# Sheet1.net
KiCad netlist of a schematic drawn in Altium Designer
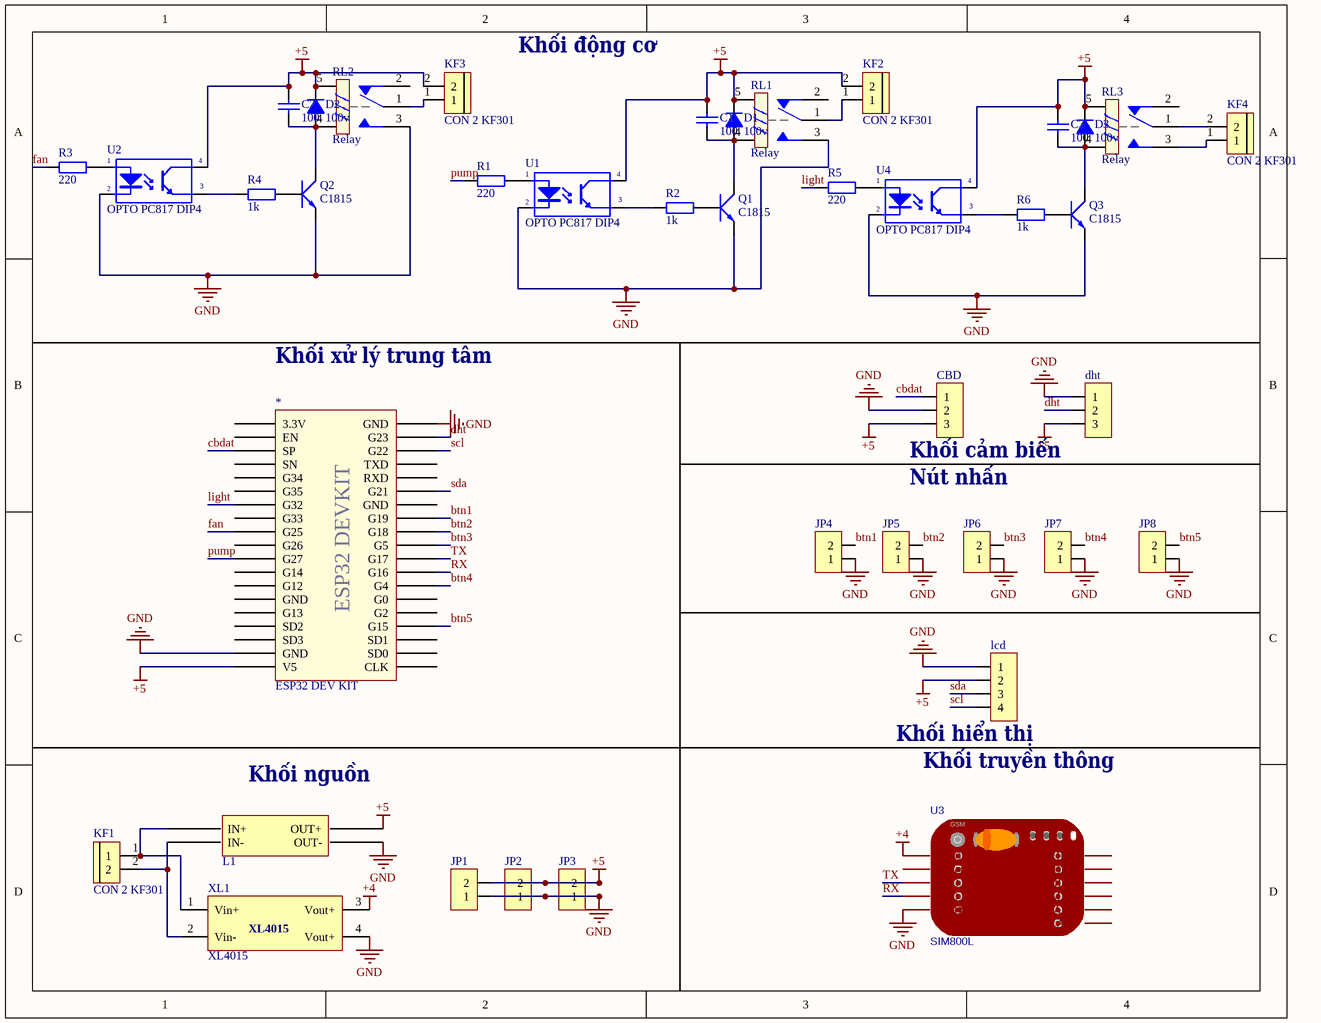
[diagram p0: Sheet1.SchDoc]

(export (version "E")
  (design (tool "Eeschema 10.0.6"))
  (components
    (comp (ref "*")
      (value "ESP32 DEV KIT")
      (footprint "ESP32 DEVKIT")
      (libsource (lib "Altium_Lib_by_KhueNguyenCreator") (part "ESP32 DEV KIT"))
    )
    (comp (ref "C1")
      (value "100")
      (footprint "tu gom")
      (description "Cắm")
      (libsource (lib "Altium_Lib_by_KhueNguyenCreator") (part "Tu gom 100 50V"))
    )
    (comp (ref "C2")
      (value "100")
      (footprint "tu gom")
      (description "Cắm")
      (libsource (lib "Altium_Lib_by_KhueNguyenCreator") (part "Tu gom 100 50V"))
    )
    (comp (ref "C3")
      (value "100")
      (footprint "tu gom")
      (description "Cắm")
      (libsource (lib "Altium_Lib_by_KhueNguyenCreator") (part "Tu gom 100 50V"))
    )
    (comp (ref "CBD")
      (value "JP 1x3 2.54")
      (footprint "JP 1x3 DT")
      (description "Cắm")
      (libsource (lib "Altium_Lib_by_KhueNguyenCreator") (part "JP 1x3 2.54 Duc Thang"))
    )
    (comp (ref "D1")
      (value "100v")
      (footprint "DIODE 1A")
      (description "Cắm")
      (libsource (lib "Altium_Lib_by_KhueNguyenCreator") (part "Diode 1N4007"))
    )
    (comp (ref "D2")
      (value "100v")
      (footprint "DIODE 1A")
      (description "Cắm")
      (libsource (lib "Altium_Lib_by_KhueNguyenCreator") (part "Diode 1N4007"))
    )
    (comp (ref "D3")
      (value "100v")
      (footprint "DIODE 1A")
      (description "Cắm")
      (libsource (lib "Altium_Lib_by_KhueNguyenCreator") (part "Diode 1N4007"))
    )
    (comp (ref "dht")
      (value "JP 1x3 2.54")
      (footprint "JP 1x3 DT")
      (description "Cắm")
      (libsource (lib "Altium_Lib_by_KhueNguyenCreator") (part "JP 1x3 2.54 Duc Thang"))
    )
    (comp (ref "JP1")
      (value "JP 1x2 2.54")
      (footprint "JP 1x2 DT")
      (description "Cắm")
      (libsource (lib "Altium_Lib_by_KhueNguyenCreator") (part "JP 1x2 2.54 Duc Thang"))
    )
    (comp (ref "JP2")
      (value "JP 1x2 2.54")
      (footprint "JP 1x2 DT")
      (description "Cắm")
      (libsource (lib "Altium_Lib_by_KhueNguyenCreator") (part "JP 1x2 2.54 Duc Thang"))
    )
    (comp (ref "JP3")
      (value "JP 1x2 2.54")
      (footprint "JP 1x2 DT")
      (description "Cắm")
      (libsource (lib "Altium_Lib_by_KhueNguyenCreator") (part "JP 1x2 2.54 Duc Thang"))
    )
    (comp (ref "JP4")
      (value "JP 1x2 2.54")
      (footprint "JP 1x2 DT")
      (description "Cắm")
      (libsource (lib "Altium_Lib_by_KhueNguyenCreator") (part "JP 1x2 2.54 Duc Thang"))
    )
    (comp (ref "JP5")
      (value "JP 1x2 2.54")
      (footprint "JP 1x2 DT")
      (description "Cắm")
      (libsource (lib "Altium_Lib_by_KhueNguyenCreator") (part "JP 1x2 2.54 Duc Thang"))
    )
    (comp (ref "JP6")
      (value "JP 1x2 2.54")
      (footprint "JP 1x2 DT")
      (description "Cắm")
      (libsource (lib "Altium_Lib_by_KhueNguyenCreator") (part "JP 1x2 2.54 Duc Thang"))
    )
    (comp (ref "JP7")
      (value "JP 1x2 2.54")
      (footprint "JP 1x2 DT")
      (description "Cắm")
      (libsource (lib "Altium_Lib_by_KhueNguyenCreator") (part "JP 1x2 2.54 Duc Thang"))
    )
    (comp (ref "JP8")
      (value "JP 1x2 2.54")
      (footprint "JP 1x2 DT")
      (description "Cắm")
      (libsource (lib "Altium_Lib_by_KhueNguyenCreator") (part "JP 1x2 2.54 Duc Thang"))
    )
    (comp (ref "KF1")
      (value "CON 2 KF301")
      (footprint "Con 2 KF301 5.08")
      (description "Cắm")
      (libsource (lib "") (part "CON 2 KF301_1"))
    )
    (comp (ref "KF2")
      (value "CON 2 KF301")
      (footprint "Con 2 KF301 5.08")
      (description "Cắm")
      (libsource (lib "Altium_Lib_by_KhueNguyenCreator") (part "CON 2 KF301"))
    )
    (comp (ref "KF3")
      (value "CON 2 KF301")
      (footprint "Con 2 KF301 5.08")
      (description "Cắm")
      (libsource (lib "Altium_Lib_by_KhueNguyenCreator") (part "CON 2 KF301"))
    )
    (comp (ref "KF4")
      (value "CON 2 KF301")
      (footprint "Con 2 KF301 5.08")
      (description "Cắm")
      (libsource (lib "Altium_Lib_by_KhueNguyenCreator") (part "CON 2 KF301"))
    )
    (comp (ref "L1")
      (value "BUCK_LM2596")
      (footprint "BUCK_LM2596")
      (libsource (lib "BUCK_LM2596_Sch") (part "BUCK_LM2596"))
    )
    (comp (ref "lcd")
      (value "JP 1x4 2.54")
      (footprint "JP 1x4 DT")
      (description "Cắm")
      (libsource (lib "Altium_Lib_by_KhueNguyenCreator") (part "JP 1x4 2.54 Duc Thang"))
    )
    (comp (ref "Q1")
      (value "C1815")
      (footprint "TO92")
      (description "NPN transistor")
      (libsource (lib "Altium_Lib_by_KhueNguyenCreator") (part "C1815"))
    )
    (comp (ref "Q2")
      (value "C1815")
      (footprint "TO92")
      (description "NPN transistor")
      (libsource (lib "Altium_Lib_by_KhueNguyenCreator") (part "C1815"))
    )
    (comp (ref "Q3")
      (value "C1815")
      (footprint "TO92")
      (description "NPN transistor")
      (libsource (lib "Altium_Lib_by_KhueNguyenCreator") (part "C1815"))
    )
    (comp (ref "R1")
      (value "220")
      (footprint "tro vach 1/4w")
      (description "Cắm")
      (libsource (lib "Altium_Lib_by_KhueNguyenCreator") (part "Tro Vach 1/4W 5% 1.2R"))
    )
    (comp (ref "R2")
      (value "1k")
      (footprint "tro vach 1/4w")
      (description "Cắm")
      (libsource (lib "Altium_Lib_by_KhueNguyenCreator") (part "Tro Vach 1/4W 5% 1.2R"))
    )
    (comp (ref "R3")
      (value "220")
      (footprint "tro vach 1/4w")
      (description "Cắm")
      (libsource (lib "Altium_Lib_by_KhueNguyenCreator") (part "Tro Vach 1/4W 5% 1.2R"))
    )
    (comp (ref "R4")
      (value "1k")
      (footprint "tro vach 1/4w")
      (description "Cắm")
      (libsource (lib "Altium_Lib_by_KhueNguyenCreator") (part "Tro Vach 1/4W 5% 1.2R"))
    )
    (comp (ref "R5")
      (value "220")
      (footprint "tro vach 1/4w")
      (description "Cắm")
      (libsource (lib "Altium_Lib_by_KhueNguyenCreator") (part "Tro Vach 1/4W 5% 1.2R"))
    )
    (comp (ref "R6")
      (value "1k")
      (footprint "tro vach 1/4w")
      (description "Cắm")
      (libsource (lib "Altium_Lib_by_KhueNguyenCreator") (part "Tro Vach 1/4W 5% 1.2R"))
    )
    (comp (ref "RL1")
      (value "Relay")
      (footprint "Relay 5 Chan SRD")
      (description "Relay 5 Chan")
      (libsource (lib "Altium_Lib_by_KhueNguyenCreator") (part "Relay 5 Chan SRD"))
    )
    (comp (ref "RL2")
      (value "Relay")
      (footprint "Relay 5 Chan SRD")
      (description "Relay 5 Chan")
      (libsource (lib "Altium_Lib_by_KhueNguyenCreator") (part "Relay 5 Chan SRD"))
    )
    (comp (ref "RL3")
      (value "Relay")
      (footprint "Relay 5 Chan SRD")
      (description "Relay 5 Chan")
      (libsource (lib "Altium_Lib_by_KhueNguyenCreator") (part "Relay 5 Chan SRD"))
    )
    (comp (ref "U1")
      (value "OPTO PC817 DIP4")
      (footprint "DIP4")
      (description "Single Opto")
      (libsource (lib "Altium_Lib_by_KhueNguyenCreator") (part "OPTO PC817 DIP4"))
    )
    (comp (ref "U2")
      (value "OPTO PC817 DIP4")
      (footprint "DIP4")
      (description "Single Opto")
      (libsource (lib "Altium_Lib_by_KhueNguyenCreator") (part "OPTO PC817 DIP4"))
    )
    (comp (ref "U3")
      (value "SIM800L")
      (footprint "SIM800L MODULE")
      (fields (field (name "BOM_SUPPLIER PART") "B01DLIJM2E") (field (name "CONTRIBUTOR") "trigui"))
      (libsource (lib "PCB_Project1") (part "SIM800L"))
    )
    (comp (ref "U4")
      (value "OPTO PC817 DIP4")
      (footprint "DIP4")
      (description "Single Opto")
      (libsource (lib "Altium_Lib_by_KhueNguyenCreator") (part "OPTO PC817 DIP4"))
    )
    (comp (ref "XL1") (value "XL4015") (footprint "XL4015") (libsource (lib "XL4015") (part "XL4015")))
  )
  (nets
    (net (code "1") (name "+4") (class "Default")
      (node (ref "U3") (pin "1") (pinfunction "VCC_1") (pintype "passive"))
      (node (ref "XL1") (pin "3") (pinfunction "Vout+_3") (pintype "passive"))
    )
    (net (code "2") (name "+5") (class "Default")
      (node (ref "*") (pin "19") (pinfunction "V5_19") (pintype "passive"))
      (node (ref "C1") (pin "1") (pinfunction "1_1") (pintype "passive"))
      (node (ref "C2") (pin "1") (pinfunction "1_1") (pintype "passive"))
      (node (ref "C3") (pin "1") (pinfunction "1_1") (pintype "passive"))
      (node (ref "CBD") (pin "3") (pinfunction "3_3") (pintype "passive"))
      (node (ref "D1") (pin "2") (pinfunction "K_2") (pintype "passive"))
      (node (ref "D2") (pin "2") (pinfunction "K_2") (pintype "passive"))
      (node (ref "D3") (pin "2") (pinfunction "K_2") (pintype "passive"))
      (node (ref "JP1") (pin "2") (pinfunction "2_2") (pintype "passive"))
      (node (ref "JP2") (pin "2") (pinfunction "2_2") (pintype "passive"))
      (node (ref "JP3") (pin "2") (pinfunction "2_2") (pintype "passive"))
      (node (ref "KF2") (pin "2") (pinfunction "2_2") (pintype "passive"))
      (node (ref "KF3") (pin "2") (pinfunction "2_2") (pintype "passive"))
      (node (ref "L1") (pin "4") (pinfunction "OUT+_4") (pintype "passive"))
      (node (ref "RL1") (pin "5") (pinfunction "5_5") (pintype "passive"))
      (node (ref "RL2") (pin "5") (pinfunction "5_5") (pintype "passive"))
      (node (ref "RL3") (pin "5") (pinfunction "5_5") (pintype "passive"))
      (node (ref "U1") (pin "4") (pinfunction "C_4") (pintype "passive"))
      (node (ref "U2") (pin "4") (pinfunction "C_4") (pintype "passive"))
      (node (ref "U4") (pin "4") (pinfunction "C_4") (pintype "passive"))
      (node (ref "dht") (pin "3") (pinfunction "3_3") (pintype "passive"))
      (node (ref "lcd") (pin "2") (pinfunction "2_2") (pintype "passive"))
    )
    (net (code "3") (name "/RX") (class "Default")
      (node (ref "*") (pin "27") (pinfunction "G16_27") (pintype "passive"))
      (node (ref "U3") (pin "4") (pinfunction "TxD_4") (pintype "passive"))
    )
    (net (code "4") (name "/TX") (class "Default")
      (node (ref "*") (pin "28") (pinfunction "G17_28") (pintype "passive"))
      (node (ref "U3") (pin "3") (pinfunction "RxD_3") (pintype "passive"))
    )
    (net (code "5") (name "/btn1") (class "Default")
      (node (ref "*") (pin "31") (pinfunction "G19_31") (pintype "passive"))
      (node (ref "JP4") (pin "2") (pinfunction "2_2") (pintype "passive"))
    )
    (net (code "6") (name "/btn2") (class "Default")
      (node (ref "*") (pin "30") (pinfunction "G18_30") (pintype "passive"))
      (node (ref "JP5") (pin "2") (pinfunction "2_2") (pintype "passive"))
    )
    (net (code "7") (name "/btn3") (class "Default")
      (node (ref "*") (pin "29") (pinfunction "G5_29") (pintype "passive"))
      (node (ref "JP6") (pin "2") (pinfunction "2_2") (pintype "passive"))
    )
    (net (code "8") (name "/btn4") (class "Default")
      (node (ref "*") (pin "26") (pinfunction "G4_26") (pintype "passive"))
      (node (ref "JP7") (pin "2") (pinfunction "2_2") (pintype "passive"))
    )
    (net (code "9") (name "/btn5") (class "Default")
      (node (ref "*") (pin "23") (pinfunction "G15_23") (pintype "passive"))
      (node (ref "JP8") (pin "2") (pinfunction "2_2") (pintype "passive"))
    )
    (net (code "10") (name "/cbdat") (class "Default")
      (node (ref "*") (pin "3") (pinfunction "SP_3") (pintype "passive"))
      (node (ref "CBD") (pin "1") (pinfunction "1_1") (pintype "passive"))
    )
    (net (code "11") (name "/dht") (class "Default")
      (node (ref "*") (pin "37") (pinfunction "G23_37") (pintype "passive"))
      (node (ref "dht") (pin "2") (pinfunction "2_2") (pintype "passive"))
    )
    (net (code "12") (name "/fan") (class "Default")
      (node (ref "*") (pin "9") (pinfunction "G25_9") (pintype "passive"))
      (node (ref "R3") (pin "1") (pinfunction "1_1") (pintype "passive"))
    )
    (net (code "13") (name "/light") (class "Default")
      (node (ref "*") (pin "7") (pinfunction "G32_7") (pintype "passive"))
      (node (ref "R5") (pin "1") (pinfunction "1_1") (pintype "passive"))
    )
    (net (code "14") (name "/pump") (class "Default")
      (node (ref "*") (pin "11") (pinfunction "G27_11") (pintype "passive"))
      (node (ref "R1") (pin "1") (pinfunction "1_1") (pintype "passive"))
    )
    (net (code "15") (name "/scl") (class "Default")
      (node (ref "*") (pin "36") (pinfunction "G22_36") (pintype "passive"))
      (node (ref "lcd") (pin "4") (pinfunction "4_4") (pintype "passive"))
    )
    (net (code "16") (name "/sda") (class "Default")
      (node (ref "*") (pin "33") (pinfunction "G21_33") (pintype "passive"))
      (node (ref "lcd") (pin "3") (pinfunction "3_3") (pintype "passive"))
    )
    (net (code "17") (name "GND") (class "Default")
      (node (ref "*") (pin "18") (pinfunction "GND_18") (pintype "passive"))
      (node (ref "*") (pin "38") (pinfunction "GND_38") (pintype "passive"))
      (node (ref "CBD") (pin "2") (pinfunction "2_2") (pintype "passive"))
      (node (ref "JP1") (pin "1") (pinfunction "1_1") (pintype "passive"))
      (node (ref "JP2") (pin "1") (pinfunction "1_1") (pintype "passive"))
      (node (ref "JP3") (pin "1") (pinfunction "1_1") (pintype "passive"))
      (node (ref "JP4") (pin "1") (pinfunction "1_1") (pintype "passive"))
      (node (ref "JP5") (pin "1") (pinfunction "1_1") (pintype "passive"))
      (node (ref "JP6") (pin "1") (pinfunction "1_1") (pintype "passive"))
      (node (ref "JP7") (pin "1") (pinfunction "1_1") (pintype "passive"))
      (node (ref "JP8") (pin "1") (pinfunction "1_1") (pintype "passive"))
      (node (ref "L1") (pin "3") (pinfunction "OUT-_3") (pintype "passive"))
      (node (ref "Q1") (pin "1") (pinfunction "E_1") (pintype "passive"))
      (node (ref "Q2") (pin "1") (pinfunction "E_1") (pintype "passive"))
      (node (ref "Q3") (pin "1") (pinfunction "E_1") (pintype "passive"))
      (node (ref "RL1") (pin "3") (pinfunction "3_3") (pintype "passive"))
      (node (ref "RL2") (pin "3") (pinfunction "3_3") (pintype "passive"))
      (node (ref "U1") (pin "2") (pinfunction "K_2") (pintype "passive"))
      (node (ref "U2") (pin "2") (pinfunction "K_2") (pintype "passive"))
      (node (ref "U3") (pin "5") (pinfunction "GND_5") (pintype "passive"))
      (node (ref "U4") (pin "2") (pinfunction "K_2") (pintype "passive"))
      (node (ref "XL1") (pin "4") (pinfunction "Vout+_4") (pintype "passive"))
      (node (ref "dht") (pin "1") (pinfunction "1_1") (pintype "passive"))
      (node (ref "lcd") (pin "1") (pinfunction "1_1") (pintype "passive"))
    )
    (net (code "18") (name "Net-(D1-A)") (class "Default")
      (node (ref "C1") (pin "2") (pinfunction "2_2") (pintype "passive"))
      (node (ref "D1") (pin "1") (pinfunction "A_1") (pintype "passive"))
      (node (ref "Q1") (pin "2") (pinfunction "C_2") (pintype "passive"))
      (node (ref "RL1") (pin "4") (pinfunction "4_4") (pintype "passive"))
    )
    (net (code "19") (name "Net-(D2-A)") (class "Default")
      (node (ref "C2") (pin "2") (pinfunction "2_2") (pintype "passive"))
      (node (ref "D2") (pin "1") (pinfunction "A_1") (pintype "passive"))
      (node (ref "Q2") (pin "2") (pinfunction "C_2") (pintype "passive"))
      (node (ref "RL2") (pin "4") (pinfunction "4_4") (pintype "passive"))
    )
    (net (code "20") (name "Net-(D3-A)") (class "Default")
      (node (ref "C3") (pin "2") (pinfunction "2_2") (pintype "passive"))
      (node (ref "D3") (pin "1") (pinfunction "A_1") (pintype "passive"))
      (node (ref "Q3") (pin "2") (pinfunction "C_2") (pintype "passive"))
      (node (ref "RL3") (pin "4") (pinfunction "4_4") (pintype "passive"))
    )
    (net (code "21") (name "Net-(KF2-Pad1)") (class "Default")
      (node (ref "KF2") (pin "1") (pinfunction "1_1") (pintype "passive"))
      (node (ref "RL1") (pin "1") (pinfunction "1_1") (pintype "passive"))
    )
    (net (code "22") (name "Net-(KF3-Pad1)") (class "Default")
      (node (ref "KF3") (pin "1") (pinfunction "1_1") (pintype "passive"))
      (node (ref "RL2") (pin "1") (pinfunction "1_1") (pintype "passive"))
    )
    (net (code "23") (name "Net-(KF4-Pad1)") (class "Default")
      (node (ref "KF4") (pin "1") (pinfunction "1_1") (pintype "passive"))
      (node (ref "RL3") (pin "3") (pinfunction "3_3") (pintype "passive"))
    )
    (net (code "24") (name "Net-(KF4-Pad2)") (class "Default")
      (node (ref "KF4") (pin "2") (pinfunction "2_2") (pintype "passive"))
      (node (ref "RL3") (pin "1") (pinfunction "1_1") (pintype "passive"))
    )
    (net (code "25") (name "Net-(L1-IN+)") (class "Default")
      (node (ref "KF1") (pin "1") (pinfunction "1_1") (pintype "passive"))
      (node (ref "L1") (pin "1") (pinfunction "IN+_1") (pintype "passive"))
      (node (ref "XL1") (pin "1") (pinfunction "Vin+_1") (pintype "passive"))
    )
    (net (code "26") (name "Net-(L1-IN-)") (class "Default")
      (node (ref "KF1") (pin "2") (pinfunction "2_2") (pintype "passive"))
      (node (ref "L1") (pin "2") (pinfunction "IN-_2") (pintype "passive"))
      (node (ref "XL1") (pin "2") (pinfunction "Vin-_2") (pintype "passive"))
    )
    (net (code "27") (name "Net-(Q1-B)") (class "Default")
      (node (ref "Q1") (pin "3") (pinfunction "B_3") (pintype "passive"))
      (node (ref "R2") (pin "2") (pinfunction "2_2") (pintype "passive"))
    )
    (net (code "28") (name "Net-(Q2-B)") (class "Default")
      (node (ref "Q2") (pin "3") (pinfunction "B_3") (pintype "passive"))
      (node (ref "R4") (pin "2") (pinfunction "2_2") (pintype "passive"))
    )
    (net (code "29") (name "Net-(Q3-B)") (class "Default")
      (node (ref "Q3") (pin "3") (pinfunction "B_3") (pintype "passive"))
      (node (ref "R6") (pin "2") (pinfunction "2_2") (pintype "passive"))
    )
    (net (code "30") (name "Net-(U1-A)") (class "Default")
      (node (ref "R1") (pin "2") (pinfunction "2_2") (pintype "passive"))
      (node (ref "U1") (pin "1") (pinfunction "A_1") (pintype "passive"))
    )
    (net (code "31") (name "Net-(U1-E)") (class "Default")
      (node (ref "R2") (pin "1") (pinfunction "1_1") (pintype "passive"))
      (node (ref "U1") (pin "3") (pinfunction "E_3") (pintype "passive"))
    )
    (net (code "32") (name "Net-(U2-A)") (class "Default")
      (node (ref "R3") (pin "2") (pinfunction "2_2") (pintype "passive"))
      (node (ref "U2") (pin "1") (pinfunction "A_1") (pintype "passive"))
    )
    (net (code "33") (name "Net-(U2-E)") (class "Default")
      (node (ref "R4") (pin "1") (pinfunction "1_1") (pintype "passive"))
      (node (ref "U2") (pin "3") (pinfunction "E_3") (pintype "passive"))
    )
    (net (code "34") (name "Net-(U4-A)") (class "Default")
      (node (ref "R5") (pin "2") (pinfunction "2_2") (pintype "passive"))
      (node (ref "U4") (pin "1") (pinfunction "A_1") (pintype "passive"))
    )
    (net (code "35") (name "Net-(U4-E)") (class "Default")
      (node (ref "R6") (pin "1") (pinfunction "1_1") (pintype "passive"))
      (node (ref "U4") (pin "3") (pinfunction "E_3") (pintype "passive"))
    )
    (net (code "36") (name "unconnected-(*-3.3V-Pad1)") (class "Default")
      (node (ref "*") (pin "1") (pinfunction "3.3V_1") (pintype "passive"))
    )
    (net (code "37") (name "unconnected-(*-CLK-Pad20)") (class "Default")
      (node (ref "*") (pin "20") (pinfunction "CLK_20") (pintype "passive"))
    )
    (net (code "38") (name "unconnected-(*-EN-Pad2)") (class "Default")
      (node (ref "*") (pin "2") (pinfunction "EN_2") (pintype "passive"))
    )
    (net (code "39") (name "unconnected-(*-G0-Pad25)") (class "Default")
      (node (ref "*") (pin "25") (pinfunction "G0_25") (pintype "passive"))
    )
    (net (code "40") (name "unconnected-(*-G2-Pad24)") (class "Default")
      (node (ref "*") (pin "24") (pinfunction "G2_24") (pintype "passive"))
    )
    (net (code "41") (name "unconnected-(*-G12-Pad13)") (class "Default")
      (node (ref "*") (pin "13") (pinfunction "G12_13") (pintype "passive"))
    )
    (net (code "42") (name "unconnected-(*-G13-Pad15)") (class "Default")
      (node (ref "*") (pin "15") (pinfunction "G13_15") (pintype "passive"))
    )
    (net (code "43") (name "unconnected-(*-G14-Pad12)") (class "Default")
      (node (ref "*") (pin "12") (pinfunction "G14_12") (pintype "passive"))
    )
    (net (code "44") (name "unconnected-(*-G26-Pad10)") (class "Default")
      (node (ref "*") (pin "10") (pinfunction "G26_10") (pintype "passive"))
    )
    (net (code "45") (name "unconnected-(*-G33-Pad8)") (class "Default")
      (node (ref "*") (pin "8") (pinfunction "G33_8") (pintype "passive"))
    )
    (net (code "46") (name "unconnected-(*-G34-Pad5)") (class "Default")
      (node (ref "*") (pin "5") (pinfunction "G34_5") (pintype "passive"))
    )
    (net (code "47") (name "unconnected-(*-G35-Pad6)") (class "Default")
      (node (ref "*") (pin "6") (pinfunction "G35_6") (pintype "passive"))
    )
    (net (code "48") (name "unconnected-(*-GND-Pad14)") (class "Default")
      (node (ref "*") (pin "14") (pinfunction "GND_14") (pintype "passive"))
    )
    (net (code "49") (name "unconnected-(*-GND-Pad32)") (class "Default")
      (node (ref "*") (pin "32") (pinfunction "GND_32") (pintype "passive"))
    )
    (net (code "50") (name "unconnected-(*-RXD-Pad34)") (class "Default")
      (node (ref "*") (pin "34") (pinfunction "RXD_34") (pintype "passive"))
    )
    (net (code "51") (name "unconnected-(*-SD0-Pad21)") (class "Default")
      (node (ref "*") (pin "21") (pinfunction "SD0_21") (pintype "passive"))
    )
    (net (code "52") (name "unconnected-(*-SD1-Pad22)") (class "Default")
      (node (ref "*") (pin "22") (pinfunction "SD1_22") (pintype "passive"))
    )
    (net (code "53") (name "unconnected-(*-SD2-Pad16)") (class "Default")
      (node (ref "*") (pin "16") (pinfunction "SD2_16") (pintype "passive"))
    )
    (net (code "54") (name "unconnected-(*-SD3-Pad17)") (class "Default")
      (node (ref "*") (pin "17") (pinfunction "SD3_17") (pintype "passive"))
    )
    (net (code "55") (name "unconnected-(*-SN-Pad4)") (class "Default")
      (node (ref "*") (pin "4") (pinfunction "SN_4") (pintype "passive"))
    )
    (net (code "56") (name "unconnected-(*-TXD-Pad35)") (class "Default")
      (node (ref "*") (pin "35") (pinfunction "TXD_35") (pintype "passive"))
    )
    (net (code "57") (name "unconnected-(RL1-Pad2)") (class "Default")
      (node (ref "RL1") (pin "2") (pinfunction "2_2") (pintype "passive"))
    )
    (net (code "58") (name "unconnected-(RL2-Pad2)") (class "Default")
      (node (ref "RL2") (pin "2") (pinfunction "2_2") (pintype "passive"))
    )
    (net (code "59") (name "unconnected-(RL3-Pad2)") (class "Default")
      (node (ref "RL3") (pin "2") (pinfunction "2_2") (pintype "passive"))
    )
    (net (code "60") (name "unconnected-(U3-DTR-Pad7)") (class "Default")
      (node (ref "U3") (pin "7") (pinfunction "DTR_7") (pintype "passive"))
    )
    (net (code "61") (name "unconnected-(U3-EAR+-Pad10)") (class "Default")
      (node (ref "U3") (pin "10") (pinfunction "EAR+_10") (pintype "passive"))
    )
    (net (code "62") (name "unconnected-(U3-EAR--Pad11)") (class "Default")
      (node (ref "U3") (pin "11") (pinfunction "EAR-_11") (pintype "passive"))
    )
    (net (code "63") (name "unconnected-(U3-MIC+-Pad8)") (class "Default")
      (node (ref "U3") (pin "8") (pinfunction "MIC+_8") (pintype "passive"))
    )
    (net (code "64") (name "unconnected-(U3-MIC--Pad9)") (class "Default")
      (node (ref "U3") (pin "9") (pinfunction "MIC-_9") (pintype "passive"))
    )
    (net (code "65") (name "unconnected-(U3-RIRG-Pad6)") (class "Default")
      (node (ref "U3") (pin "6") (pinfunction "RIRG_6") (pintype "passive"))
    )
    (net (code "66") (name "unconnected-(U3-Reset-Pad2)") (class "Default")
      (node (ref "U3") (pin "2") (pinfunction "Reset_2") (pintype "passive"))
    )
  )
)
